# PM_proto_1.net
KiCad netlist of a schematic drawn in EAGLE
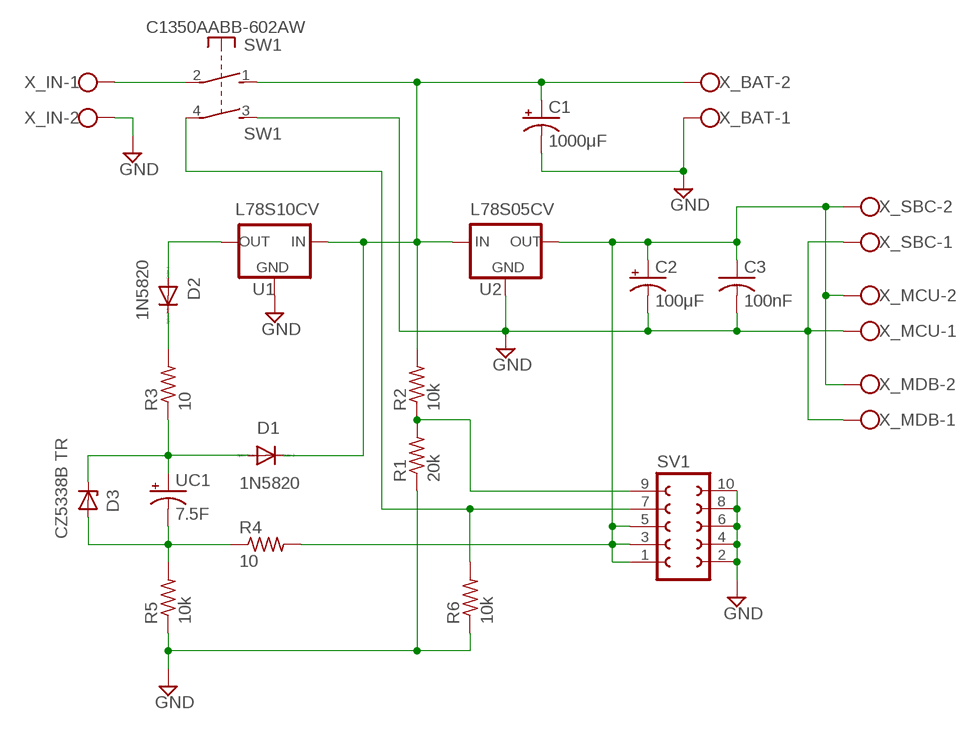
[diagram p0: schematic, sheet 1]

(export (version "E")
  (design (tool "Eeschema 10.0.6"))
  (components
    (comp (ref "C1")
      (value "1000μF")
      (footprint "eagle-import:E2,5-6E")
      (libsource (lib "eagle-import") (part "CPOL-USE2,5-6E"))
    )
    (comp (ref "C2")
      (value "100μF")
      (footprint "eagle-import:E2,5-6E")
      (libsource (lib "eagle-import") (part "CPOL-USE2,5-6E"))
    )
    (comp (ref "C3")
      (value "100nF")
      (footprint "eagle-import:C025-024X044")
      (libsource (lib "eagle-import") (part "C-US025-024X044"))
    )
    (comp (ref "D1")
      (value "1N5820")
      (footprint "eagle-import:DO41-10")
      (libsource (lib "eagle-import") (part "1N4004"))
    )
    (comp (ref "D2")
      (value "1N5820")
      (footprint "eagle-import:DO41-10")
      (libsource (lib "eagle-import") (part "1N4004"))
    )
    (comp (ref "D3")
      (value "CZ5338B TR")
      (footprint "eagle-import:DO41Z10")
      (libsource (lib "eagle-import") (part "1N4728"))
    )
    (comp (ref "R1")
      (value "20k")
      (footprint "eagle-import:0204_7")
      (libsource (lib "eagle-import") (part "R-US_0204/7"))
    )
    (comp (ref "R2")
      (value "10k")
      (footprint "eagle-import:0204_7")
      (libsource (lib "eagle-import") (part "R-US_0204/7"))
    )
    (comp (ref "R3")
      (value "10")
      (footprint "eagle-import:0204_7")
      (libsource (lib "eagle-import") (part "R-US_0204/7"))
    )
    (comp (ref "R4")
      (value "10")
      (footprint "eagle-import:0204_7")
      (libsource (lib "eagle-import") (part "R-US_0204/7"))
    )
    (comp (ref "R5")
      (value "10k")
      (footprint "eagle-import:0204_7")
      (libsource (lib "eagle-import") (part "R-US_0204/7"))
    )
    (comp (ref "R6")
      (value "10k")
      (footprint "eagle-import:0204_7")
      (libsource (lib "eagle-import") (part "R-US_0204/7"))
    )
    (comp (ref "SV1")
      (value "FE05-2")
      (footprint "eagle-import:FE05-2")
      (libsource (lib "eagle-import") (part "FE05-2"))
    )
    (comp (ref "SW1")
      (value "C1350AABB-602AW")
      (footprint "eagle-import:PVA1F")
      (libsource (lib "eagle-import") (part "PVA1"))
    )
    (comp (ref "U1")
      (value "L78S10CV")
      (footprint "eagle-import:78XXS")
      (libsource (lib "eagle-import") (part "78XXS"))
    )
    (comp (ref "U2")
      (value "L78S05CV")
      (footprint "eagle-import:78XXS")
      (fields (field (name "SPICEPREFIX") "J"))
      (libsource (lib "eagle-import") (part "78XXS"))
    )
    (comp (ref "UC1")
      (value "7.5F")
      (footprint "eagle-import:ETR4")
      (libsource (lib "eagle-import") (part "CPOL-USETR4"))
    )
    (comp (ref "X_BAT")
      (value "W237-102")
      (footprint "eagle-import:W237-102")
      (fields (field (name "MPN") "237-102"))
      (libsource (lib "eagle-import") (part "W237-102"))
    )
    (comp (ref "X_IN")
      (value "W237-102")
      (footprint "eagle-import:W237-102")
      (fields (field (name "MPN") "237-102"))
      (libsource (lib "eagle-import") (part "W237-102"))
    )
    (comp (ref "X_MCU")
      (value "W237-102")
      (footprint "eagle-import:W237-102")
      (fields (field (name "MPN") "237-102"))
      (libsource (lib "eagle-import") (part "W237-102"))
    )
    (comp (ref "X_MDB")
      (value "W237-102")
      (footprint "eagle-import:W237-102")
      (fields (field (name "MPN") "237-102"))
      (libsource (lib "eagle-import") (part "W237-102"))
    )
    (comp (ref "X_SBC")
      (value "W237-102")
      (footprint "eagle-import:W237-102")
      (fields (field (name "MPN") "237-102"))
      (libsource (lib "eagle-import") (part "W237-102"))
    )
  )
  (nets
    (net (code "1") (name "GND") (class "Default")
      (node (ref "C1") (pin "-") (pinfunction "-_-") (pintype "passive"))
      (node (ref "C2") (pin "-") (pinfunction "-_-") (pintype "passive"))
      (node (ref "C3") (pin "2") (pinfunction "2_2") (pintype "passive"))
      (node (ref "R1") (pin "1") (pinfunction "1_1") (pintype "passive"))
      (node (ref "R5") (pin "1") (pinfunction "1_1") (pintype "passive"))
      (node (ref "R6") (pin "1") (pinfunction "1_1") (pintype "passive"))
      (node (ref "SV1") (pin "10") (pinfunction "10_10") (pintype "passive"))
      (node (ref "SV1") (pin "2") (pinfunction "2_2") (pintype "passive"))
      (node (ref "SV1") (pin "4") (pinfunction "4_4") (pintype "passive"))
      (node (ref "SV1") (pin "6") (pinfunction "6_6") (pintype "passive"))
      (node (ref "SV1") (pin "8") (pinfunction "8_8") (pintype "passive"))
      (node (ref "SW1") (pin "3") (pinfunction "S_3") (pintype "passive"))
      (node (ref "U1") (pin "GND") (pinfunction "GND_GND") (pintype "input"))
      (node (ref "U2") (pin "GND") (pinfunction "GND_GND") (pintype "input"))
      (node (ref "X_BAT") (pin "1") (pinfunction "KL_1") (pintype "passive"))
      (node (ref "X_IN") (pin "2") (pinfunction "KL_2") (pintype "passive"))
      (node (ref "X_MCU") (pin "1") (pinfunction "KL_1") (pintype "passive"))
      (node (ref "X_MDB") (pin "1") (pinfunction "KL_1") (pintype "passive"))
      (node (ref "X_SBC") (pin "1") (pinfunction "KL_1") (pintype "passive"))
    )
    (net (code "2") (name "Net-(D1-PadA)") (class "Default")
      (node (ref "D1") (pin "A") (pinfunction "A_A") (pintype "passive"))
      (node (ref "D3") (pin "C") (pinfunction "C_C") (pintype "passive"))
      (node (ref "R3") (pin "1") (pinfunction "1_1") (pintype "passive"))
      (node (ref "UC1") (pin "+") (pinfunction "+_+") (pintype "passive"))
    )
    (net (code "3") (name "Net-(D2-PadA)") (class "Default")
      (node (ref "D2") (pin "A") (pinfunction "A_A") (pintype "passive"))
      (node (ref "U1") (pin "OUT") (pinfunction "OUT_OUT") (pintype "passive"))
    )
    (net (code "4") (name "Net-(D2-PadC)") (class "Default")
      (node (ref "D2") (pin "C") (pinfunction "C_C") (pintype "passive"))
      (node (ref "R3") (pin "2") (pinfunction "2_2") (pintype "passive"))
    )
    (net (code "5") (name "Net-(D3-PadA)") (class "Default")
      (node (ref "D3") (pin "A") (pinfunction "A_A") (pintype "passive"))
      (node (ref "R4") (pin "1") (pinfunction "1_1") (pintype "passive"))
      (node (ref "R5") (pin "2") (pinfunction "2_2") (pintype "passive"))
      (node (ref "UC1") (pin "-") (pinfunction "-_-") (pintype "passive"))
    )
    (net (code "6") (name "Net-(R1-Pad2)") (class "Default")
      (node (ref "R1") (pin "2") (pinfunction "2_2") (pintype "passive"))
      (node (ref "R2") (pin "1") (pinfunction "1_1") (pintype "passive"))
      (node (ref "SV1") (pin "9") (pinfunction "9_9") (pintype "passive"))
    )
    (net (code "7") (name "Net-(SW1A-P)") (class "Default")
      (node (ref "SW1") (pin "2") (pinfunction "P_2") (pintype "passive"))
      (node (ref "X_IN") (pin "1") (pinfunction "KL_1") (pintype "passive"))
    )
    (net (code "8") (name "Net-(SW1A-S)") (class "Default")
      (node (ref "C1") (pin "+") (pinfunction "+_+") (pintype "passive"))
      (node (ref "D1") (pin "C") (pinfunction "C_C") (pintype "passive"))
      (node (ref "R2") (pin "2") (pinfunction "2_2") (pintype "passive"))
      (node (ref "SW1") (pin "1") (pinfunction "S_1") (pintype "passive"))
      (node (ref "U1") (pin "IN") (pinfunction "IN_IN") (pintype "input"))
      (node (ref "U2") (pin "IN") (pinfunction "IN_IN") (pintype "input"))
      (node (ref "X_BAT") (pin "2") (pinfunction "KL_2") (pintype "passive"))
    )
    (net (code "9") (name "Net-(SW1B-P)") (class "Default")
      (node (ref "R6") (pin "2") (pinfunction "2_2") (pintype "passive"))
      (node (ref "SV1") (pin "7") (pinfunction "7_7") (pintype "passive"))
      (node (ref "SW1") (pin "4") (pinfunction "P_4") (pintype "passive"))
    )
    (net (code "10") (name "Net-(X_MCUB-KL)") (class "Default")
      (node (ref "C2") (pin "+") (pinfunction "+_+") (pintype "passive"))
      (node (ref "C3") (pin "1") (pinfunction "1_1") (pintype "passive"))
      (node (ref "R4") (pin "2") (pinfunction "2_2") (pintype "passive"))
      (node (ref "SV1") (pin "1") (pinfunction "1_1") (pintype "passive"))
      (node (ref "SV1") (pin "3") (pinfunction "3_3") (pintype "passive"))
      (node (ref "SV1") (pin "5") (pinfunction "5_5") (pintype "passive"))
      (node (ref "U2") (pin "OUT") (pinfunction "OUT_OUT") (pintype "passive"))
      (node (ref "X_MCU") (pin "2") (pinfunction "KL_2") (pintype "passive"))
      (node (ref "X_MDB") (pin "2") (pinfunction "KL_2") (pintype "passive"))
      (node (ref "X_SBC") (pin "2") (pinfunction "KL_2") (pintype "passive"))
    )
  )
)
